# QCopterMV-Expand_Sch.net
KiCad netlist of a schematic drawn in Altium Designer
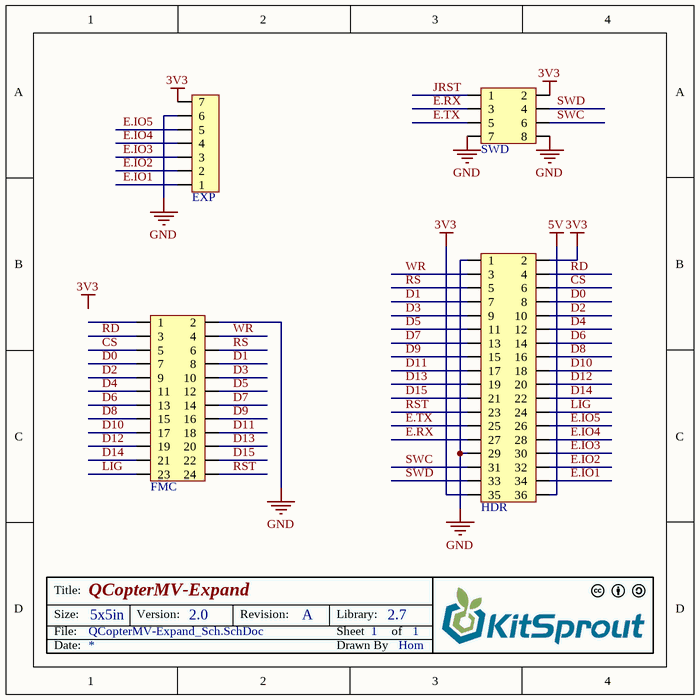
[diagram p0: QCopterMV-Expand_Sch.SchDoc]

(export (version "E")
  (design (tool "Eeschema 10.0.6"))
  (components
    (comp (ref "EXP")
      (value "HDR1x7_2.54")
      (footprint "PCB_ConnectorHDR:HDR1X7_2.54_180H")
      (description "Header")
      (libsource (lib "SCH_ConnectorHDR") (part "HDR1x7_2.54T"))
    )
    (comp (ref "FMC")
      (value "HDR2x12_2.54")
      (footprint "PCB_ConnectorHDR:HDR2X12_2.54_180HF")
      (description "Header")
      (libsource (lib "SCH_ConnectorHDR") (part "HDR2x12_2.54"))
    )
    (comp (ref "HDR")
      (value "HDR2x18_1.27")
      (footprint "PCB_ConnectorHDR:HDR2X18_1.27_180H")
      (description "Header")
      (libsource (lib "SCH_ConnectorHDR") (part "HDR2x18_1.27"))
    )
    (comp (ref "SWD")
      (value "HDR2x4_2.54")
      (footprint "PCB_ConnectorHDR:HDR2X4_2.54_180HF")
      (description "Header")
      (libsource (lib "SCH_ConnectorHDR") (part "HDR2x4_2.54"))
    )
  )
  (nets
    (net (code "1") (name "/CS") (class "Default")
      (node (ref "FMC") (pin "5") (pinfunction "5_5") (pintype "passive"))
      (node (ref "HDR") (pin "6") (pinfunction "6_6") (pintype "passive"))
    )
    (net (code "2") (name "/D0") (class "Default")
      (node (ref "FMC") (pin "7") (pinfunction "7_7") (pintype "passive"))
      (node (ref "HDR") (pin "8") (pinfunction "8_8") (pintype "passive"))
    )
    (net (code "3") (name "/D1") (class "Default")
      (node (ref "FMC") (pin "8") (pinfunction "8_8") (pintype "passive"))
      (node (ref "HDR") (pin "7") (pinfunction "7_7") (pintype "passive"))
    )
    (net (code "4") (name "/D2") (class "Default")
      (node (ref "FMC") (pin "9") (pinfunction "9_9") (pintype "passive"))
      (node (ref "HDR") (pin "10") (pinfunction "10_10") (pintype "passive"))
    )
    (net (code "5") (name "/D3") (class "Default")
      (node (ref "FMC") (pin "10") (pinfunction "10_10") (pintype "passive"))
      (node (ref "HDR") (pin "9") (pinfunction "9_9") (pintype "passive"))
    )
    (net (code "6") (name "/D4") (class "Default")
      (node (ref "FMC") (pin "11") (pinfunction "11_11") (pintype "passive"))
      (node (ref "HDR") (pin "12") (pinfunction "12_12") (pintype "passive"))
    )
    (net (code "7") (name "/D5") (class "Default")
      (node (ref "FMC") (pin "12") (pinfunction "12_12") (pintype "passive"))
      (node (ref "HDR") (pin "11") (pinfunction "11_11") (pintype "passive"))
    )
    (net (code "8") (name "/D6") (class "Default")
      (node (ref "FMC") (pin "13") (pinfunction "13_13") (pintype "passive"))
      (node (ref "HDR") (pin "14") (pinfunction "14_14") (pintype "passive"))
    )
    (net (code "9") (name "/D7") (class "Default")
      (node (ref "FMC") (pin "14") (pinfunction "14_14") (pintype "passive"))
      (node (ref "HDR") (pin "13") (pinfunction "13_13") (pintype "passive"))
    )
    (net (code "10") (name "/D8") (class "Default")
      (node (ref "FMC") (pin "15") (pinfunction "15_15") (pintype "passive"))
      (node (ref "HDR") (pin "16") (pinfunction "16_16") (pintype "passive"))
    )
    (net (code "11") (name "/D9") (class "Default")
      (node (ref "FMC") (pin "16") (pinfunction "16_16") (pintype "passive"))
      (node (ref "HDR") (pin "15") (pinfunction "15_15") (pintype "passive"))
    )
    (net (code "12") (name "/D10") (class "Default")
      (node (ref "FMC") (pin "17") (pinfunction "17_17") (pintype "passive"))
      (node (ref "HDR") (pin "18") (pinfunction "18_18") (pintype "passive"))
    )
    (net (code "13") (name "/D11") (class "Default")
      (node (ref "FMC") (pin "18") (pinfunction "18_18") (pintype "passive"))
      (node (ref "HDR") (pin "17") (pinfunction "17_17") (pintype "passive"))
    )
    (net (code "14") (name "/D12") (class "Default")
      (node (ref "FMC") (pin "19") (pinfunction "19_19") (pintype "passive"))
      (node (ref "HDR") (pin "20") (pinfunction "20_20") (pintype "passive"))
    )
    (net (code "15") (name "/D13") (class "Default")
      (node (ref "FMC") (pin "20") (pinfunction "20_20") (pintype "passive"))
      (node (ref "HDR") (pin "19") (pinfunction "19_19") (pintype "passive"))
    )
    (net (code "16") (name "/D14") (class "Default")
      (node (ref "FMC") (pin "21") (pinfunction "21_21") (pintype "passive"))
      (node (ref "HDR") (pin "22") (pinfunction "22_22") (pintype "passive"))
    )
    (net (code "17") (name "/D15") (class "Default")
      (node (ref "FMC") (pin "22") (pinfunction "22_22") (pintype "passive"))
      (node (ref "HDR") (pin "21") (pinfunction "21_21") (pintype "passive"))
    )
    (net (code "18") (name "/E.IO1") (class "Default")
      (node (ref "EXP") (pin "1") (pinfunction "1_1") (pintype "passive"))
      (node (ref "HDR") (pin "34") (pinfunction "34_34") (pintype "passive"))
    )
    (net (code "19") (name "/E.IO2") (class "Default")
      (node (ref "EXP") (pin "2") (pinfunction "2_2") (pintype "passive"))
      (node (ref "HDR") (pin "32") (pinfunction "32_32") (pintype "passive"))
    )
    (net (code "20") (name "/E.IO3") (class "Default")
      (node (ref "EXP") (pin "3") (pinfunction "3_3") (pintype "passive"))
      (node (ref "HDR") (pin "30") (pinfunction "30_30") (pintype "passive"))
    )
    (net (code "21") (name "/E.IO4") (class "Default")
      (node (ref "EXP") (pin "4") (pinfunction "4_4") (pintype "passive"))
      (node (ref "HDR") (pin "28") (pinfunction "28_28") (pintype "passive"))
    )
    (net (code "22") (name "/E.IO5") (class "Default")
      (node (ref "EXP") (pin "5") (pinfunction "5_5") (pintype "passive"))
      (node (ref "HDR") (pin "26") (pinfunction "26_26") (pintype "passive"))
    )
    (net (code "23") (name "/E.RX") (class "Default")
      (node (ref "HDR") (pin "27") (pinfunction "27_27") (pintype "passive"))
      (node (ref "SWD") (pin "3") (pinfunction "3_3") (pintype "passive"))
    )
    (net (code "24") (name "/E.TX") (class "Default")
      (node (ref "HDR") (pin "25") (pinfunction "25_25") (pintype "passive"))
      (node (ref "SWD") (pin "5") (pinfunction "5_5") (pintype "passive"))
    )
    (net (code "25") (name "/JRST") (class "Default")
      (node (ref "SWD") (pin "1") (pinfunction "1_1") (pintype "passive"))
    )
    (net (code "26") (name "/LIG") (class "Default")
      (node (ref "FMC") (pin "23") (pinfunction "23_23") (pintype "passive"))
      (node (ref "HDR") (pin "24") (pinfunction "24_24") (pintype "passive"))
    )
    (net (code "27") (name "/RD") (class "Default")
      (node (ref "FMC") (pin "3") (pinfunction "3_3") (pintype "passive"))
      (node (ref "HDR") (pin "4") (pinfunction "4_4") (pintype "passive"))
    )
    (net (code "28") (name "/RS") (class "Default")
      (node (ref "FMC") (pin "6") (pinfunction "6_6") (pintype "passive"))
      (node (ref "HDR") (pin "5") (pinfunction "5_5") (pintype "passive"))
    )
    (net (code "29") (name "/RST") (class "Default")
      (node (ref "FMC") (pin "24") (pinfunction "24_24") (pintype "passive"))
      (node (ref "HDR") (pin "23") (pinfunction "23_23") (pintype "passive"))
    )
    (net (code "30") (name "/SWC") (class "Default")
      (node (ref "HDR") (pin "31") (pinfunction "31_31") (pintype "passive"))
      (node (ref "SWD") (pin "6") (pinfunction "6_6") (pintype "passive"))
    )
    (net (code "31") (name "/SWD") (class "Default")
      (node (ref "HDR") (pin "33") (pinfunction "33_33") (pintype "passive"))
      (node (ref "SWD") (pin "4") (pinfunction "4_4") (pintype "passive"))
    )
    (net (code "32") (name "/WR") (class "Default")
      (node (ref "FMC") (pin "4") (pinfunction "4_4") (pintype "passive"))
      (node (ref "HDR") (pin "3") (pinfunction "3_3") (pintype "passive"))
    )
    (net (code "33") (name "3V3") (class "Default")
      (node (ref "EXP") (pin "7") (pinfunction "7_7") (pintype "passive"))
      (node (ref "HDR") (pin "2") (pinfunction "2_2") (pintype "passive"))
      (node (ref "HDR") (pin "35") (pinfunction "35_35") (pintype "passive"))
      (node (ref "SWD") (pin "2") (pinfunction "2_2") (pintype "passive"))
    )
    (net (code "34") (name "5V") (class "Default")
      (node (ref "HDR") (pin "36") (pinfunction "36_36") (pintype "passive"))
    )
    (net (code "35") (name "GND") (class "Default")
      (node (ref "EXP") (pin "6") (pinfunction "6_6") (pintype "passive"))
      (node (ref "FMC") (pin "2") (pinfunction "2_2") (pintype "passive"))
      (node (ref "HDR") (pin "1") (pinfunction "1_1") (pintype "passive"))
      (node (ref "HDR") (pin "29") (pinfunction "29_29") (pintype "passive"))
      (node (ref "SWD") (pin "7") (pinfunction "7_7") (pintype "passive"))
      (node (ref "SWD") (pin "8") (pinfunction "8_8") (pintype "passive"))
    )
    (net (code "36") (name "unconnected-(FMC-Pad1)") (class "Default")
      (node (ref "FMC") (pin "1") (pinfunction "1_1") (pintype "passive"))
    )
  )
)
